# single_hr_mux_d1.net
KiCad netlist of a schematic drawn in EAGLE
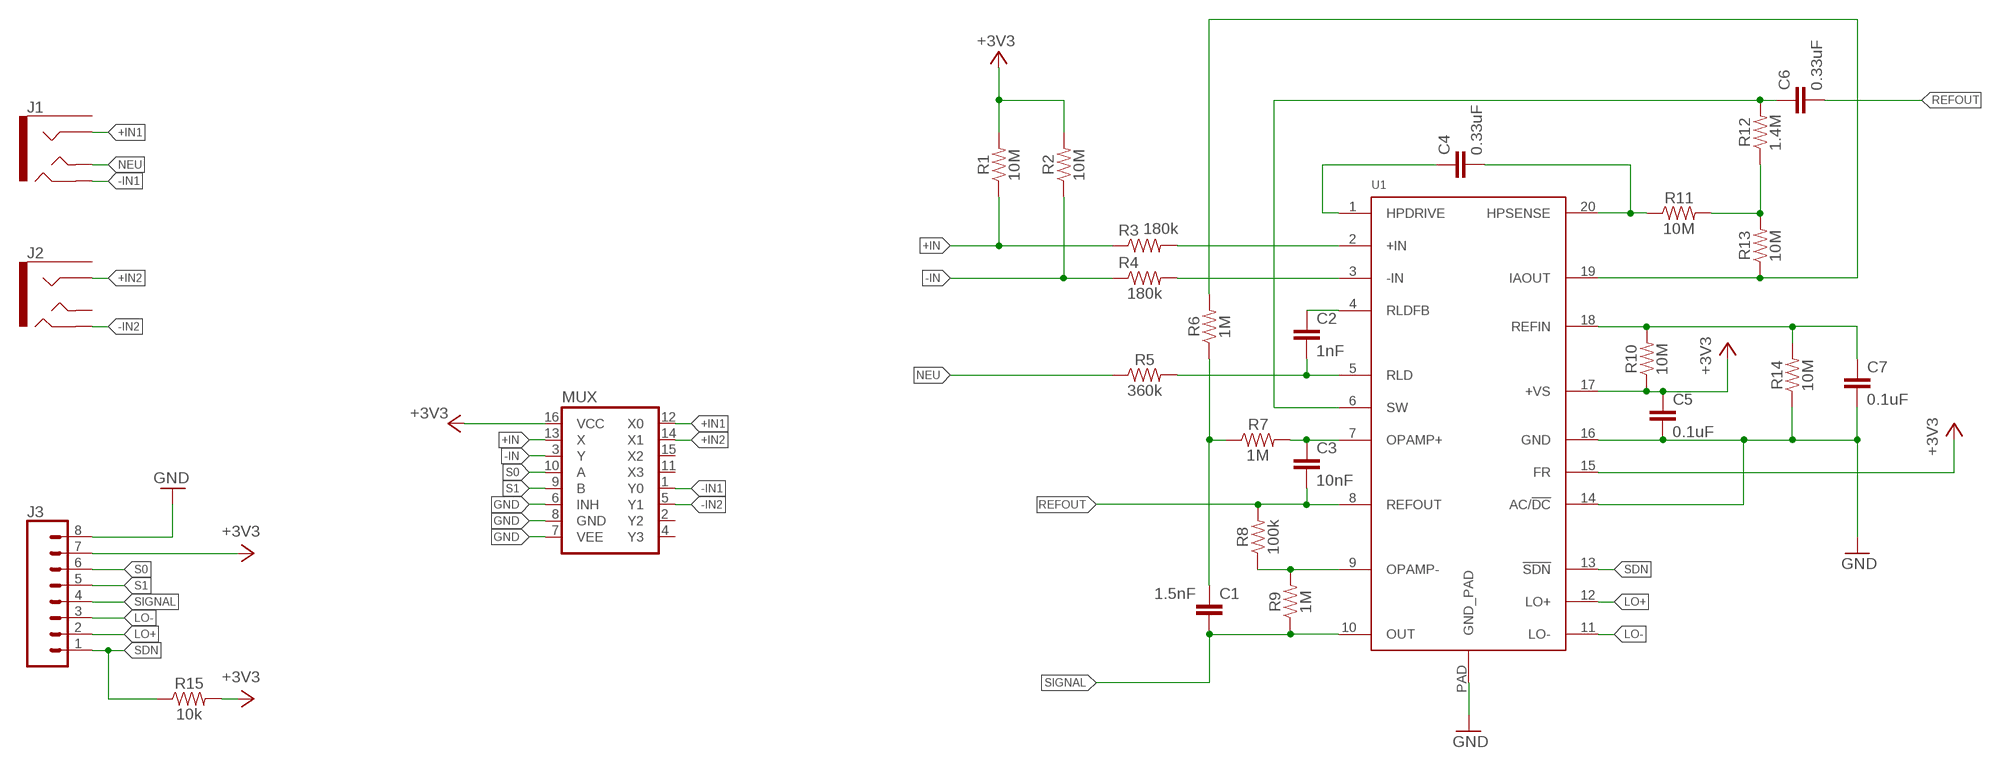
[diagram p0: schematic, sheet 1]

(export (version "E")
  (design (tool "Eeschema 10.0.6"))
  (components
    (comp (ref "C1")
      (value "1.5nF")
      (footprint "eagle-import:0603-CAP")
      (libsource (lib "eagle-import") (part "CAP0603-CAP"))
    )
    (comp (ref "C2")
      (value "1nF")
      (footprint "eagle-import:0603-CAP")
      (libsource (lib "eagle-import") (part "CAP0603-CAP"))
    )
    (comp (ref "C3")
      (value "10nF")
      (footprint "eagle-import:0603-CAP")
      (libsource (lib "eagle-import") (part "CAP0603-CAP"))
    )
    (comp (ref "C4")
      (value "0.33uF")
      (footprint "eagle-import:0805")
      (libsource (lib "eagle-import") (part "CAP0805"))
    )
    (comp (ref "C5")
      (value "0.1uF")
      (footprint "eagle-import:0603-CAP")
      (libsource (lib "eagle-import") (part "CAP0603-CAP"))
    )
    (comp (ref "C6")
      (value "0.33uF")
      (footprint "eagle-import:0805")
      (libsource (lib "eagle-import") (part "CAP0805"))
    )
    (comp (ref "C7")
      (value "0.1uF")
      (footprint "eagle-import:0603-CAP")
      (libsource (lib "eagle-import") (part "CAP0603-CAP"))
    )
    (comp (ref "J1")
      (value "AUDIO_JACK_TRRSSMD_RA")
      (footprint "eagle-import:AUDIO_JACK_3.5MM_TRRS_SMD_RA")
      (libsource (lib "eagle-import") (part "AUDIO_JACK_TRRSSMD_RA"))
    )
    (comp (ref "J2")
      (value "AUDIO_JACK_TRRSSMD_RA")
      (footprint "eagle-import:AUDIO_JACK_3.5MM_TRRS_SMD_RA")
      (libsource (lib "eagle-import") (part "AUDIO_JACK_TRRSSMD_RA"))
    )
    (comp (ref "J3")
      (value "CONN_08\"")
      (footprint "eagle-import:1X08")
      (libsource (lib "eagle-import") (part "CONN_08{dblquote}"))
    )
    (comp (ref "MUX")
      (value "74HC4052D")
      (footprint "eagle-import:SO16")
      (libsource (lib "eagle-import") (part "744052DHC"))
    )
    (comp (ref "R1")
      (value "10M")
      (footprint "eagle-import:0603")
      (libsource (lib "eagle-import") (part "RESISTOR0603"))
    )
    (comp (ref "R2")
      (value "10M")
      (footprint "eagle-import:0603")
      (libsource (lib "eagle-import") (part "RESISTOR0603"))
    )
    (comp (ref "R3")
      (value "180k")
      (footprint "eagle-import:0603")
      (libsource (lib "eagle-import") (part "RESISTOR0603"))
    )
    (comp (ref "R4")
      (value "180k")
      (footprint "eagle-import:0603")
      (libsource (lib "eagle-import") (part "RESISTOR0603"))
    )
    (comp (ref "R5")
      (value "360k")
      (footprint "eagle-import:0603")
      (libsource (lib "eagle-import") (part "RESISTOR0603"))
    )
    (comp (ref "R6")
      (value "1M")
      (footprint "eagle-import:0603")
      (libsource (lib "eagle-import") (part "RESISTOR0603"))
    )
    (comp (ref "R7")
      (value "1M")
      (footprint "eagle-import:0603")
      (libsource (lib "eagle-import") (part "RESISTOR0603"))
    )
    (comp (ref "R8")
      (value "100k")
      (footprint "eagle-import:0603")
      (libsource (lib "eagle-import") (part "RESISTOR0603"))
    )
    (comp (ref "R9")
      (value "1M")
      (footprint "eagle-import:0603")
      (libsource (lib "eagle-import") (part "RESISTOR0603"))
    )
    (comp (ref "R10")
      (value "10M")
      (footprint "eagle-import:0603")
      (libsource (lib "eagle-import") (part "RESISTOR0603"))
    )
    (comp (ref "R11")
      (value "10M")
      (footprint "eagle-import:0603")
      (libsource (lib "eagle-import") (part "RESISTOR0603"))
    )
    (comp (ref "R12")
      (value "1.4M")
      (footprint "eagle-import:0603")
      (libsource (lib "eagle-import") (part "RESISTOR0603"))
    )
    (comp (ref "R13")
      (value "10M")
      (footprint "eagle-import:0603")
      (libsource (lib "eagle-import") (part "RESISTOR0603"))
    )
    (comp (ref "R14")
      (value "10M")
      (footprint "eagle-import:0603")
      (libsource (lib "eagle-import") (part "RESISTOR0603"))
    )
    (comp (ref "R15")
      (value "10k")
      (footprint "eagle-import:0603")
      (libsource (lib "eagle-import") (part "10KOHM-0603-1/10W-1%"))
    )
    (comp (ref "U1")
      (value "AD8232ACPZ-R7")
      (footprint "eagle-import:LFCSP_20")
      (libsource (lib "eagle-import") (part "AD8232"))
    )
  )
  (nets
    (net (code "1") (name "+3V3") (class "Default")
      (node (ref "C5") (pin "1") (pinfunction "1_1") (pintype "passive"))
      (node (ref "J3") (pin "7") (pinfunction "7_7") (pintype "passive"))
      (node (ref "MUX") (pin "16") (pinfunction "VCC_16") (pintype "power_in"))
      (node (ref "R1") (pin "2") (pinfunction "2_2") (pintype "passive"))
      (node (ref "R10") (pin "1") (pinfunction "1_1") (pintype "passive"))
      (node (ref "R15") (pin "2") (pinfunction "2_2") (pintype "passive"))
      (node (ref "R2") (pin "2") (pinfunction "2_2") (pintype "passive"))
      (node (ref "U1") (pin "15") (pinfunction "FR_15") (pintype "bidirectional"))
      (node (ref "U1") (pin "17") (pinfunction "+VS_17") (pintype "bidirectional"))
    )
    (net (code "2") (name "+IN") (class "Default")
      (node (ref "MUX") (pin "13") (pinfunction "X_13") (pintype "bidirectional"))
      (node (ref "R1") (pin "1") (pinfunction "1_1") (pintype "passive"))
      (node (ref "R3") (pin "1") (pinfunction "1_1") (pintype "passive"))
    )
    (net (code "3") (name "+IN1") (class "Default")
      (node (ref "J1") (pin "RING1") (pinfunction "RING1_RING1") (pintype "bidirectional"))
      (node (ref "MUX") (pin "12") (pinfunction "X0_12") (pintype "bidirectional"))
    )
    (net (code "4") (name "+IN2") (class "Default")
      (node (ref "J2") (pin "RING1") (pinfunction "RING1_RING1") (pintype "bidirectional"))
      (node (ref "MUX") (pin "14") (pinfunction "X1_14") (pintype "bidirectional"))
    )
    (net (code "5") (name "-IN") (class "Default")
      (node (ref "MUX") (pin "3") (pinfunction "Y_3") (pintype "bidirectional"))
      (node (ref "R2") (pin "1") (pinfunction "1_1") (pintype "passive"))
      (node (ref "R4") (pin "1") (pinfunction "1_1") (pintype "passive"))
    )
    (net (code "6") (name "-IN1") (class "Default")
      (node (ref "J1") (pin "RING2") (pinfunction "RING2_RING2") (pintype "bidirectional"))
      (node (ref "MUX") (pin "1") (pinfunction "Y0_1") (pintype "bidirectional"))
    )
    (net (code "7") (name "-IN2") (class "Default")
      (node (ref "J2") (pin "RING2") (pinfunction "RING2_RING2") (pintype "bidirectional"))
      (node (ref "MUX") (pin "5") (pinfunction "Y1_5") (pintype "bidirectional"))
    )
    (net (code "8") (name "GND") (class "Default")
      (node (ref "C5") (pin "2") (pinfunction "2_2") (pintype "passive"))
      (node (ref "C7") (pin "2") (pinfunction "2_2") (pintype "passive"))
      (node (ref "J3") (pin "8") (pinfunction "8_8") (pintype "passive"))
      (node (ref "MUX") (pin "6") (pinfunction "INH_6") (pintype "input"))
      (node (ref "MUX") (pin "7") (pinfunction "VEE_7") (pintype "power_in"))
      (node (ref "MUX") (pin "8") (pinfunction "GND_8") (pintype "power_in"))
      (node (ref "R14") (pin "1") (pinfunction "1_1") (pintype "passive"))
      (node (ref "U1") (pin "14") (pinfunction "AC/~{DC}_14") (pintype "bidirectional"))
      (node (ref "U1") (pin "16") (pinfunction "GND_16") (pintype "bidirectional"))
      (node (ref "U1") (pin "PAD") (pinfunction "GND_PAD_PAD") (pintype "bidirectional"))
    )
    (net (code "9") (name "LO+") (class "Default")
      (node (ref "J3") (pin "2") (pinfunction "2_2") (pintype "passive"))
      (node (ref "U1") (pin "12") (pinfunction "LO+_12") (pintype "bidirectional"))
    )
    (net (code "10") (name "LO-") (class "Default")
      (node (ref "J3") (pin "3") (pinfunction "3_3") (pintype "passive"))
      (node (ref "U1") (pin "11") (pinfunction "LO-_11") (pintype "bidirectional"))
    )
    (net (code "11") (name "NEU") (class "Default")
      (node (ref "J1") (pin "TIP") (pinfunction "TIP_TIP") (pintype "bidirectional"))
      (node (ref "R5") (pin "1") (pinfunction "1_1") (pintype "passive"))
    )
    (net (code "12") (name "Net-(C1-Pad1)") (class "Default")
      (node (ref "C1") (pin "1") (pinfunction "1_1") (pintype "passive"))
      (node (ref "R6") (pin "1") (pinfunction "1_1") (pintype "passive"))
      (node (ref "R7") (pin "1") (pinfunction "1_1") (pintype "passive"))
    )
    (net (code "13") (name "Net-(R11-Pad2)") (class "Default")
      (node (ref "R11") (pin "2") (pinfunction "2_2") (pintype "passive"))
      (node (ref "R12") (pin "1") (pinfunction "1_1") (pintype "passive"))
      (node (ref "R13") (pin "2") (pinfunction "2_2") (pintype "passive"))
    )
    (net (code "14") (name "Net-(U1-+IN)") (class "Default")
      (node (ref "R3") (pin "2") (pinfunction "2_2") (pintype "passive"))
      (node (ref "U1") (pin "2") (pinfunction "+IN_2") (pintype "bidirectional"))
    )
    (net (code "15") (name "Net-(U1--IN)") (class "Default")
      (node (ref "R4") (pin "2") (pinfunction "2_2") (pintype "passive"))
      (node (ref "U1") (pin "3") (pinfunction "-IN_3") (pintype "bidirectional"))
    )
    (net (code "16") (name "Net-(U1-HPDRIVE)") (class "Default")
      (node (ref "C4") (pin "1") (pinfunction "1_1") (pintype "passive"))
      (node (ref "U1") (pin "1") (pinfunction "HPDRIVE_1") (pintype "bidirectional"))
    )
    (net (code "17") (name "Net-(U1-HPSENSE)") (class "Default")
      (node (ref "C4") (pin "2") (pinfunction "2_2") (pintype "passive"))
      (node (ref "R11") (pin "1") (pinfunction "1_1") (pintype "passive"))
      (node (ref "U1") (pin "20") (pinfunction "HPSENSE_20") (pintype "bidirectional"))
    )
    (net (code "18") (name "Net-(U1-IAOUT)") (class "Default")
      (node (ref "R13") (pin "1") (pinfunction "1_1") (pintype "passive"))
      (node (ref "R6") (pin "2") (pinfunction "2_2") (pintype "passive"))
      (node (ref "U1") (pin "19") (pinfunction "IAOUT_19") (pintype "bidirectional"))
    )
    (net (code "19") (name "Net-(U1-OPAMP+)") (class "Default")
      (node (ref "C3") (pin "1") (pinfunction "1_1") (pintype "passive"))
      (node (ref "R7") (pin "2") (pinfunction "2_2") (pintype "passive"))
      (node (ref "U1") (pin "7") (pinfunction "OPAMP+_7") (pintype "bidirectional"))
    )
    (net (code "20") (name "Net-(U1-OPAMP-)") (class "Default")
      (node (ref "R8") (pin "1") (pinfunction "1_1") (pintype "passive"))
      (node (ref "R9") (pin "2") (pinfunction "2_2") (pintype "passive"))
      (node (ref "U1") (pin "9") (pinfunction "OPAMP-_9") (pintype "bidirectional"))
    )
    (net (code "21") (name "Net-(U1-REFIN)") (class "Default")
      (node (ref "C7") (pin "1") (pinfunction "1_1") (pintype "passive"))
      (node (ref "R10") (pin "2") (pinfunction "2_2") (pintype "passive"))
      (node (ref "R14") (pin "2") (pinfunction "2_2") (pintype "passive"))
      (node (ref "U1") (pin "18") (pinfunction "REFIN_18") (pintype "bidirectional"))
    )
    (net (code "22") (name "Net-(U1-RLD)") (class "Default")
      (node (ref "C2") (pin "2") (pinfunction "2_2") (pintype "passive"))
      (node (ref "R5") (pin "2") (pinfunction "2_2") (pintype "passive"))
      (node (ref "U1") (pin "5") (pinfunction "RLD_5") (pintype "bidirectional"))
    )
    (net (code "23") (name "Net-(U1-RLDFB)") (class "Default")
      (node (ref "C2") (pin "1") (pinfunction "1_1") (pintype "passive"))
      (node (ref "U1") (pin "4") (pinfunction "RLDFB_4") (pintype "bidirectional"))
    )
    (net (code "24") (name "Net-(U1-SW)") (class "Default")
      (node (ref "C6") (pin "1") (pinfunction "1_1") (pintype "passive"))
      (node (ref "R12") (pin "2") (pinfunction "2_2") (pintype "passive"))
      (node (ref "U1") (pin "6") (pinfunction "SW_6") (pintype "bidirectional"))
    )
    (net (code "25") (name "REFOUT") (class "Default")
      (node (ref "C3") (pin "2") (pinfunction "2_2") (pintype "passive"))
      (node (ref "C6") (pin "2") (pinfunction "2_2") (pintype "passive"))
      (node (ref "R8") (pin "2") (pinfunction "2_2") (pintype "passive"))
      (node (ref "U1") (pin "8") (pinfunction "REFOUT_8") (pintype "bidirectional"))
    )
    (net (code "26") (name "S0") (class "Default")
      (node (ref "J3") (pin "6") (pinfunction "6_6") (pintype "passive"))
      (node (ref "MUX") (pin "10") (pinfunction "A_10") (pintype "input"))
    )
    (net (code "27") (name "S1") (class "Default")
      (node (ref "J3") (pin "5") (pinfunction "5_5") (pintype "passive"))
      (node (ref "MUX") (pin "9") (pinfunction "B_9") (pintype "input"))
    )
    (net (code "28") (name "SDN") (class "Default")
      (node (ref "J3") (pin "1") (pinfunction "1_1") (pintype "passive"))
      (node (ref "R15") (pin "1") (pinfunction "1_1") (pintype "passive"))
      (node (ref "U1") (pin "13") (pinfunction "~{SDN}_13") (pintype "bidirectional"))
    )
    (net (code "29") (name "SIGNAL") (class "Default")
      (node (ref "C1") (pin "2") (pinfunction "2_2") (pintype "passive"))
      (node (ref "J3") (pin "4") (pinfunction "4_4") (pintype "passive"))
      (node (ref "R9") (pin "1") (pinfunction "1_1") (pintype "passive"))
      (node (ref "U1") (pin "10") (pinfunction "OUT_10") (pintype "bidirectional"))
    )
    (net (code "30") (name "unconnected-(J1-PadEARTH)") (class "Default")
      (node (ref "J1") (pin "EARTH") (pinfunction "EARTH_EARTH") (pintype "bidirectional"))
    )
    (net (code "31") (name "unconnected-(J2-PadEARTH)") (class "Default")
      (node (ref "J2") (pin "EARTH") (pinfunction "EARTH_EARTH") (pintype "bidirectional"))
    )
    (net (code "32") (name "unconnected-(J2-PadTIP)") (class "Default")
      (node (ref "J2") (pin "TIP") (pinfunction "TIP_TIP") (pintype "bidirectional"))
    )
    (net (code "33") (name "unconnected-(MUX-X2-Pad15)") (class "Default")
      (node (ref "MUX") (pin "15") (pinfunction "X2_15") (pintype "bidirectional"))
    )
    (net (code "34") (name "unconnected-(MUX-X3-Pad11)") (class "Default")
      (node (ref "MUX") (pin "11") (pinfunction "X3_11") (pintype "bidirectional"))
    )
    (net (code "35") (name "unconnected-(MUX-Y2-Pad2)") (class "Default")
      (node (ref "MUX") (pin "2") (pinfunction "Y2_2") (pintype "bidirectional"))
    )
    (net (code "36") (name "unconnected-(MUX-Y3-Pad4)") (class "Default")
      (node (ref "MUX") (pin "4") (pinfunction "Y3_4") (pintype "bidirectional"))
    )
  )
)
